# DAC.net
KiCad netlist of a schematic drawn in Altium Designer
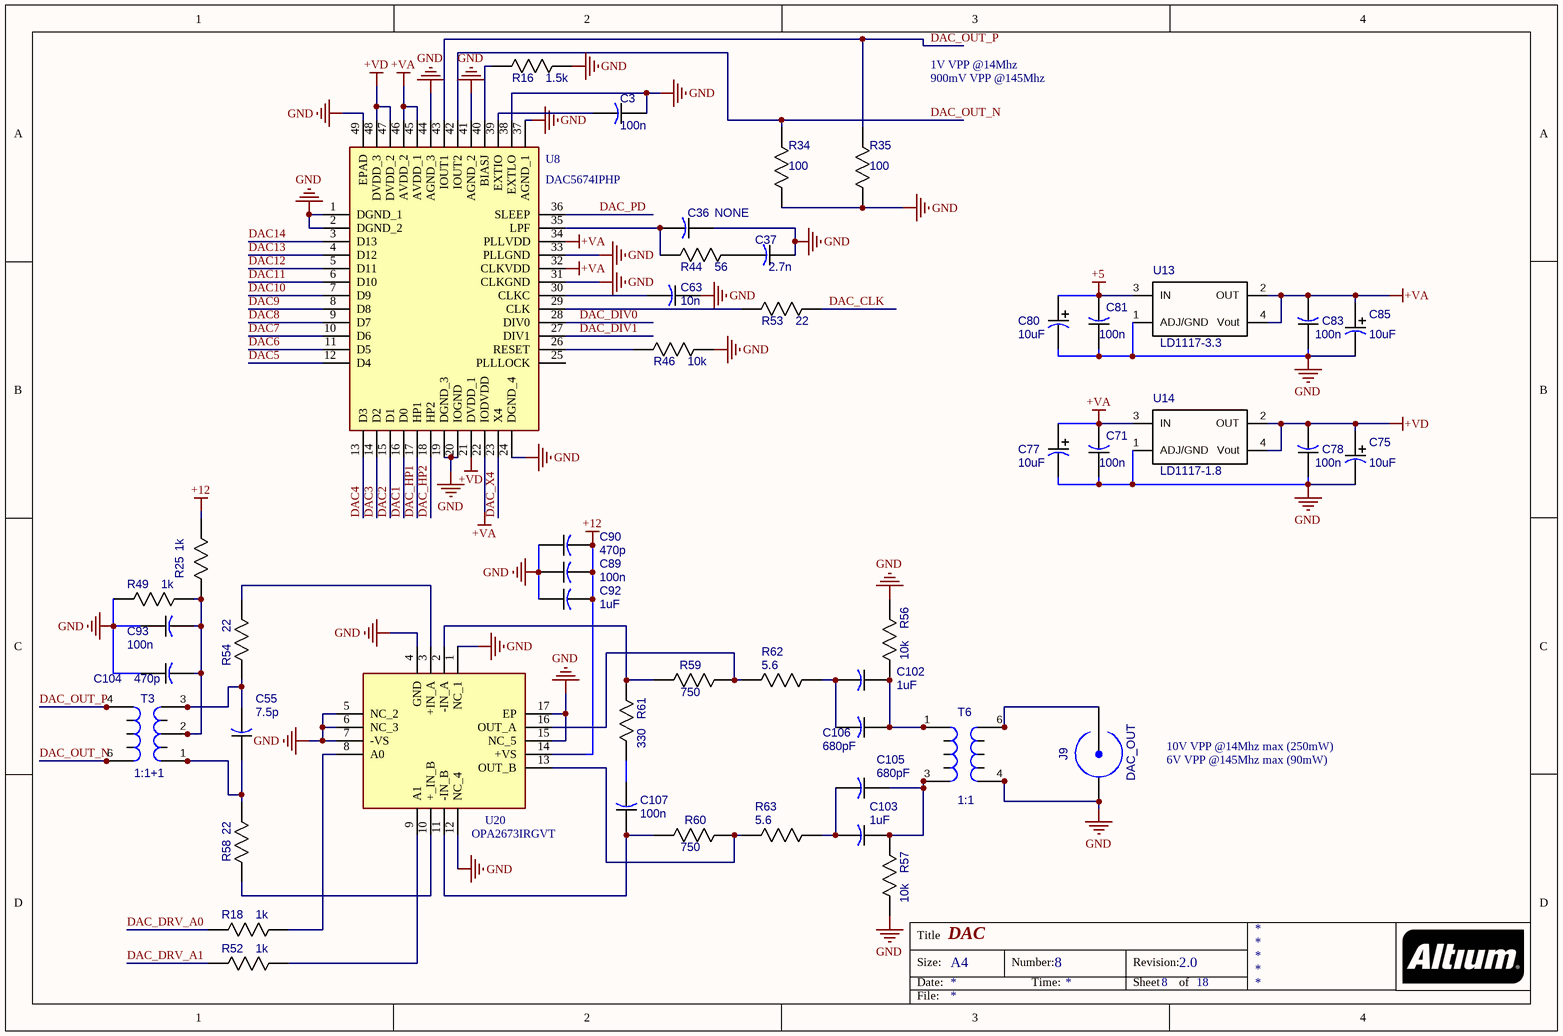
[diagram p0: DAC.SchDoc]

(export (version "E")
  (design (tool "Eeschema 10.0.6"))
  (components
    (comp (ref "C3")
      (value "100n")
      (footprint "CAP_0805")
      (description "CAP_0805")
      (libsource (lib "*") (part "CAP_0805"))
    )
    (comp (ref "C36")
      (value "NONE")
      (footprint "CAP_0805")
      (description "CAP_0805")
      (libsource (lib "*") (part "CAP_0805"))
    )
    (comp (ref "C37")
      (value "2.7n")
      (footprint "CAP_0805")
      (description "CAP_0805")
      (libsource (lib "*") (part "CAP_0805"))
    )
    (comp (ref "C55")
      (value "7.5p")
      (footprint "CAP_0805")
      (description "CAP_0805")
      (libsource (lib "*") (part "CAP_0805"))
    )
    (comp (ref "C63")
      (value "10n")
      (footprint "CAP_0805")
      (description "CAP_0805")
      (libsource (lib "*") (part "CAP_0805"))
    )
    (comp (ref "C71")
      (value "100n")
      (footprint "CAP_0805")
      (description "CAP_0805")
      (libsource (lib "*") (part "CAP_0805"))
    )
    (comp (ref "C75")
      (value "10uF")
      (footprint "EEEFC_sizeB")
      (description "EEEFC_sizeB")
      (libsource (lib "*") (part "EEEFC_sizeB"))
    )
    (comp (ref "C77")
      (value "10uF")
      (footprint "EEEFC_sizeB")
      (description "EEEFC_sizeB")
      (libsource (lib "*") (part "EEEFC_sizeB"))
    )
    (comp (ref "C78")
      (value "100n")
      (footprint "CAP_0805")
      (description "CAP_0805")
      (libsource (lib "*") (part "CAP_0805"))
    )
    (comp (ref "C80")
      (value "10uF")
      (footprint "EEEFC_sizeB")
      (description "EEEFC_sizeB")
      (libsource (lib "*") (part "EEEFC_sizeB"))
    )
    (comp (ref "C81")
      (value "100n")
      (footprint "CAP_0805")
      (description "CAP_0805")
      (libsource (lib "*") (part "CAP_0805"))
    )
    (comp (ref "C83")
      (value "100n")
      (footprint "CAP_0805")
      (description "CAP_0805")
      (libsource (lib "*") (part "CAP_0805"))
    )
    (comp (ref "C85")
      (value "10uF")
      (footprint "EEEFC_sizeB")
      (description "EEEFC_sizeB")
      (libsource (lib "*") (part "EEEFC_sizeB"))
    )
    (comp (ref "C89")
      (value "100n")
      (footprint "CAP_0805")
      (description "CAP_0805")
      (libsource (lib "*") (part "CAP_0805"))
    )
    (comp (ref "C90")
      (value "470p")
      (footprint "CAP_0805")
      (description "CAP_0805")
      (libsource (lib "*") (part "CAP_0805"))
    )
    (comp (ref "C92")
      (value "1uF")
      (footprint "CAP_0805")
      (description "CAP_0805")
      (libsource (lib "*") (part "CAP_0805"))
    )
    (comp (ref "C93")
      (value "100n")
      (footprint "CAP_0805")
      (description "CAP_0805")
      (libsource (lib "*") (part "CAP_0805"))
    )
    (comp (ref "C102")
      (value "1uF")
      (footprint "CAP_1206")
      (description "CAP_1206")
      (libsource (lib "*") (part "CAP_1206"))
    )
    (comp (ref "C103")
      (value "1uF")
      (footprint "CAP_1206")
      (description "CAP_1206")
      (libsource (lib "*") (part "CAP_1206"))
    )
    (comp (ref "C104")
      (value "470p")
      (footprint "CAP_0805")
      (description "CAP_0805")
      (libsource (lib "*") (part "CAP_0805"))
    )
    (comp (ref "C105")
      (value "680pF")
      (footprint "CAP_1206")
      (description "CAP_1206")
      (libsource (lib "*") (part "CAP_1206"))
    )
    (comp (ref "C106")
      (value "680pF")
      (footprint "CAP_1206")
      (description "CAP_1206")
      (libsource (lib "*") (part "CAP_1206"))
    )
    (comp (ref "C107")
      (value "100n")
      (footprint "CAP_0805")
      (description "CAP_0805")
      (libsource (lib "*") (part "CAP_0805"))
    )
    (comp (ref "J9")
      (value "DAC_OUT")
      (footprint "31-5431")
      (description "SMA")
      (libsource (lib "RF-UNIT_1") (part "31-5431"))
    )
    (comp (ref "R16")
      (value "1.5k")
      (footprint "RES_0805")
      (description "RES_0805")
      (libsource (lib "*") (part "RES_0805"))
    )
    (comp (ref "R18")
      (value "1k")
      (footprint "RES_0805")
      (description "RES_0805")
      (libsource (lib "*") (part "RES_0805"))
    )
    (comp (ref "R25")
      (value "1k")
      (footprint "RES_0805")
      (description "RES_0805")
      (libsource (lib "*") (part "RES_0805"))
    )
    (comp (ref "R34")
      (value "100")
      (footprint "RES_0805")
      (description "RES_0805")
      (libsource (lib "*") (part "RES_0805"))
    )
    (comp (ref "R35")
      (value "100")
      (footprint "RES_0805")
      (description "RES_0805")
      (libsource (lib "*") (part "RES_0805"))
    )
    (comp (ref "R44")
      (value "56")
      (footprint "RES_0805")
      (description "RES_0805")
      (libsource (lib "*") (part "RES_0805"))
    )
    (comp (ref "R46")
      (value "10k")
      (footprint "RES_0805")
      (description "RES_0805")
      (libsource (lib "*") (part "RES_0805"))
    )
    (comp (ref "R49")
      (value "1k")
      (footprint "RES_0805")
      (description "RES_0805")
      (libsource (lib "*") (part "RES_0805"))
    )
    (comp (ref "R52")
      (value "1k")
      (footprint "RES_0805")
      (description "RES_0805")
      (libsource (lib "*") (part "RES_0805"))
    )
    (comp (ref "R53")
      (value "22")
      (footprint "RES_0805")
      (description "RES_0805")
      (libsource (lib "*") (part "RES_0805"))
    )
    (comp (ref "R54")
      (value "22")
      (footprint "RES_0805")
      (description "RES_0805")
      (libsource (lib "*") (part "RES_0805"))
    )
    (comp (ref "R56")
      (value "10k")
      (footprint "RES_0805")
      (description "RES_0805")
      (libsource (lib "*") (part "RES_0805"))
    )
    (comp (ref "R57")
      (value "10k")
      (footprint "RES_0805")
      (description "RES_0805")
      (libsource (lib "*") (part "RES_0805"))
    )
    (comp (ref "R58")
      (value "22")
      (footprint "RES_0805")
      (description "RES_0805")
      (libsource (lib "*") (part "RES_0805"))
    )
    (comp (ref "R59")
      (value "750")
      (footprint "RES_0805")
      (description "RES_0805")
      (libsource (lib "*") (part "RES_0805"))
    )
    (comp (ref "R60")
      (value "750")
      (footprint "RES_0805")
      (description "RES_0805")
      (libsource (lib "*") (part "RES_0805"))
    )
    (comp (ref "R61")
      (value "330")
      (footprint "RES_0805")
      (description "RES_0805")
      (libsource (lib "*") (part "RES_0805"))
    )
    (comp (ref "R62")
      (value "5.6")
      (footprint "RES_1206")
      (description "RES_1206")
      (libsource (lib "*") (part "RES_1206"))
    )
    (comp (ref "R63")
      (value "5.6")
      (footprint "RES_1206")
      (description "RES_1206")
      (libsource (lib "*") (part "RES_1206"))
    )
    (comp (ref "T3")
      (value "1:1+1")
      (footprint "TRANSF_ACORE2")
      (description "Transformer")
      (libsource (lib "MOTHERBOARD_1") (part "TRANSF_ACORE2"))
    )
    (comp (ref "T6")
      (value "1:1")
      (footprint "TRANSF_ACORE")
      (description "Transformer")
      (libsource (lib "MOTHERBOARD_1") (part "TRANSF_ACORE"))
    )
    (comp (ref "U8")
      (value "DAC5674IPHP")
      (footprint "SamacSys:QFP50P900X900X100-49N")
      (description "Integrated Circuit")
      (libsource (lib "*") (part "DAC5674IPHP"))
    )
    (comp (ref "U13")
      (value "LD1117-3.3")
      (footprint "LT1117CST-3.3")
      (description "LT1117CST-3.3")
      (libsource (lib "*") (part "LT1117CST-3.3"))
    )
    (comp (ref "U14")
      (value "LD1117-1.8")
      (footprint "LT1117CST-3.3")
      (description "LT1117CST-1.8")
      (libsource (lib "*") (part "LT1117CST-3.3"))
    )
    (comp (ref "U20")
      (value "OPA2673IRGVT")
      (footprint "SamacSys:QFN65P400X400X100-17N-D")
      (description "Integrated Circuit")
      (fields
        (field (name "MOUSER PART NUMBER") "595-OPA2673IRGVT")
        (field (name "RS PART NUMBER") "8122587P")
      )
      (libsource (lib "*") (part "OPA2673IRGVT"))
    )
  )
  (nets
    (net (code "1") (name "+5") (class "Default")
      (node (ref "C80") (pin "1") (pinfunction "PLUS_1") (pintype "passive"))
      (node (ref "C81") (pin "2") (pinfunction "2_2") (pintype "passive"))
      (node (ref "U13") (pin "3") (pinfunction "IN_3") (pintype "passive"))
    )
    (net (code "2") (name "+12") (class "Default")
      (node (ref "C89") (pin "2") (pinfunction "2_2") (pintype "passive"))
      (node (ref "C90") (pin "2") (pinfunction "2_2") (pintype "passive"))
      (node (ref "C92") (pin "2") (pinfunction "2_2") (pintype "passive"))
      (node (ref "R25") (pin "2") (pinfunction "2_2") (pintype "passive"))
      (node (ref "U20") (pin "14") (pinfunction "+VS_14") (pintype "passive"))
    )
    (net (code "3") (name "+VA") (class "Default")
      (node (ref "C71") (pin "2") (pinfunction "2_2") (pintype "passive"))
      (node (ref "C77") (pin "1") (pinfunction "PLUS_1") (pintype "passive"))
      (node (ref "C83") (pin "2") (pinfunction "2_2") (pintype "passive"))
      (node (ref "C85") (pin "1") (pinfunction "PLUS_1") (pintype "passive"))
      (node (ref "U13") (pin "2") (pinfunction "OUT_2") (pintype "passive"))
      (node (ref "U13") (pin "4") (pinfunction "Vout_4") (pintype "passive"))
      (node (ref "U14") (pin "3") (pinfunction "IN_3") (pintype "passive"))
      (node (ref "U8") (pin "22") (pinfunction "IODVDD_22") (pintype "passive"))
      (node (ref "U8") (pin "32") (pinfunction "CLKVDD_32") (pintype "passive"))
      (node (ref "U8") (pin "34") (pinfunction "PLLVDD_34") (pintype "passive"))
      (node (ref "U8") (pin "45") (pinfunction "AVDD_1_45") (pintype "passive"))
      (node (ref "U8") (pin "46") (pinfunction "AVDD_2_46") (pintype "passive"))
    )
    (net (code "4") (name "+VD") (class "Default")
      (node (ref "C75") (pin "1") (pinfunction "PLUS_1") (pintype "passive"))
      (node (ref "C78") (pin "2") (pinfunction "2_2") (pintype "passive"))
      (node (ref "U14") (pin "2") (pinfunction "OUT_2") (pintype "passive"))
      (node (ref "U14") (pin "4") (pinfunction "Vout_4") (pintype "passive"))
      (node (ref "U8") (pin "21") (pinfunction "DVDD_1_21") (pintype "passive"))
      (node (ref "U8") (pin "47") (pinfunction "DVDD_2_47") (pintype "passive"))
      (node (ref "U8") (pin "48") (pinfunction "DVDD_3_48") (pintype "passive"))
    )
    (net (code "5") (name "/DAC1") (class "Default")
      (node (ref "U8") (pin "16") (pinfunction "D0_16") (pintype "passive"))
    )
    (net (code "6") (name "/DAC2") (class "Default")
      (node (ref "U8") (pin "15") (pinfunction "D1_15") (pintype "passive"))
    )
    (net (code "7") (name "/DAC3") (class "Default")
      (node (ref "U8") (pin "14") (pinfunction "D2_14") (pintype "passive"))
    )
    (net (code "8") (name "/DAC4") (class "Default")
      (node (ref "U8") (pin "13") (pinfunction "D3_13") (pintype "passive"))
    )
    (net (code "9") (name "/DAC5") (class "Default")
      (node (ref "U8") (pin "12") (pinfunction "D4_12") (pintype "passive"))
    )
    (net (code "10") (name "/DAC6") (class "Default")
      (node (ref "U8") (pin "11") (pinfunction "D5_11") (pintype "passive"))
    )
    (net (code "11") (name "/DAC7") (class "Default")
      (node (ref "U8") (pin "10") (pinfunction "D6_10") (pintype "passive"))
    )
    (net (code "12") (name "/DAC8") (class "Default")
      (node (ref "U8") (pin "9") (pinfunction "D7_9") (pintype "passive"))
    )
    (net (code "13") (name "/DAC9") (class "Default")
      (node (ref "U8") (pin "8") (pinfunction "D8_8") (pintype "passive"))
    )
    (net (code "14") (name "/DAC10") (class "Default")
      (node (ref "U8") (pin "7") (pinfunction "D9_7") (pintype "passive"))
    )
    (net (code "15") (name "/DAC11") (class "Default")
      (node (ref "U8") (pin "6") (pinfunction "D10_6") (pintype "passive"))
    )
    (net (code "16") (name "/DAC12") (class "Default")
      (node (ref "U8") (pin "5") (pinfunction "D11_5") (pintype "passive"))
    )
    (net (code "17") (name "/DAC13") (class "Default")
      (node (ref "U8") (pin "4") (pinfunction "D12_4") (pintype "passive"))
    )
    (net (code "18") (name "/DAC14") (class "Default")
      (node (ref "U8") (pin "3") (pinfunction "D13_3") (pintype "passive"))
    )
    (net (code "19") (name "/DAC_CLK") (class "Default")
      (node (ref "R53") (pin "1") (pinfunction "1_1") (pintype "passive"))
    )
    (net (code "20") (name "/DAC_DIV0") (class "Default")
      (node (ref "U8") (pin "28") (pinfunction "DIV0_28") (pintype "passive"))
    )
    (net (code "21") (name "/DAC_DIV1") (class "Default")
      (node (ref "U8") (pin "27") (pinfunction "DIV1_27") (pintype "passive"))
    )
    (net (code "22") (name "/DAC_DRV_A0") (class "Default")
      (node (ref "R18") (pin "1") (pinfunction "1_1") (pintype "passive"))
    )
    (net (code "23") (name "/DAC_DRV_A1") (class "Default")
      (node (ref "R52") (pin "1") (pinfunction "1_1") (pintype "passive"))
    )
    (net (code "24") (name "/DAC_HP1") (class "Default")
      (node (ref "U8") (pin "17") (pinfunction "HP1_17") (pintype "passive"))
    )
    (net (code "25") (name "/DAC_HP2") (class "Default")
      (node (ref "U8") (pin "18") (pinfunction "HP2_18") (pintype "passive"))
    )
    (net (code "26") (name "/DAC_OUT_N") (class "Default")
      (node (ref "R34") (pin "2") (pinfunction "2_2") (pintype "passive"))
      (node (ref "T3") (pin "10") (pinfunction "0_10") (pintype "passive"))
      (node (ref "T3") (pin "6") (pinfunction "P2_6") (pintype "passive"))
      (node (ref "U8") (pin "42") (pinfunction "IOUT2_42") (pintype "passive"))
    )
    (net (code "27") (name "/DAC_OUT_P") (class "Default")
      (node (ref "R35") (pin "2") (pinfunction "2_2") (pintype "passive"))
      (node (ref "T3") (pin "11") (pinfunction "0_11") (pintype "passive"))
      (node (ref "T3") (pin "4") (pinfunction "P1_4") (pintype "passive"))
      (node (ref "U8") (pin "43") (pinfunction "IOUT1_43") (pintype "passive"))
    )
    (net (code "28") (name "/DAC_PD") (class "Default")
      (node (ref "U8") (pin "36") (pinfunction "SLEEP_36") (pintype "passive"))
    )
    (net (code "29") (name "/DAC_X4") (class "Default")
      (node (ref "U8") (pin "23") (pinfunction "X4_23") (pintype "passive"))
    )
    (net (code "30") (name "GND") (class "Default")
      (node (ref "C104") (pin "1") (pinfunction "1_1") (pintype "passive"))
      (node (ref "C3") (pin "1") (pinfunction "1_1") (pintype "passive"))
      (node (ref "C36") (pin "1") (pinfunction "1_1") (pintype "passive"))
      (node (ref "C37") (pin "1") (pinfunction "1_1") (pintype "passive"))
      (node (ref "C63") (pin "1") (pinfunction "1_1") (pintype "passive"))
      (node (ref "C71") (pin "1") (pinfunction "1_1") (pintype "passive"))
      (node (ref "C75") (pin "2") (pinfunction "MINUS_2") (pintype "passive"))
      (node (ref "C77") (pin "2") (pinfunction "MINUS_2") (pintype "passive"))
      (node (ref "C78") (pin "1") (pinfunction "1_1") (pintype "passive"))
      (node (ref "C80") (pin "2") (pinfunction "MINUS_2") (pintype "passive"))
      (node (ref "C81") (pin "1") (pinfunction "1_1") (pintype "passive"))
      (node (ref "C83") (pin "1") (pinfunction "1_1") (pintype "passive"))
      (node (ref "C85") (pin "2") (pinfunction "MINUS_2") (pintype "passive"))
      (node (ref "C89") (pin "1") (pinfunction "1_1") (pintype "passive"))
      (node (ref "C90") (pin "1") (pinfunction "1_1") (pintype "passive"))
      (node (ref "C92") (pin "1") (pinfunction "1_1") (pintype "passive"))
      (node (ref "C93") (pin "1") (pinfunction "1_1") (pintype "passive"))
      (node (ref "J9") (pin "1") (pinfunction "GND_1") (pintype "passive"))
      (node (ref "J9") (pin "2") (pinfunction "GND_2") (pintype "passive"))
      (node (ref "J9") (pin "3") (pinfunction "GND_3") (pintype "passive"))
      (node (ref "J9") (pin "4") (pinfunction "GND_4") (pintype "passive"))
      (node (ref "R16") (pin "1") (pinfunction "1_1") (pintype "passive"))
      (node (ref "R34") (pin "1") (pinfunction "1_1") (pintype "passive"))
      (node (ref "R35") (pin "1") (pinfunction "1_1") (pintype "passive"))
      (node (ref "R46") (pin "1") (pinfunction "1_1") (pintype "passive"))
      (node (ref "R49") (pin "2") (pinfunction "2_2") (pintype "passive"))
      (node (ref "R56") (pin "1") (pinfunction "1_1") (pintype "passive"))
      (node (ref "R57") (pin "2") (pinfunction "2_2") (pintype "passive"))
      (node (ref "T6") (pin "11") (pinfunction "0_11") (pintype "passive"))
      (node (ref "T6") (pin "4") (pinfunction "S2_4") (pintype "passive"))
      (node (ref "U13") (pin "1") (pinfunction "ADJ/GND_1") (pintype "passive"))
      (node (ref "U14") (pin "1") (pinfunction "ADJ/GND_1") (pintype "passive"))
      (node (ref "U20") (pin "1") (pinfunction "NC_1_1") (pintype "passive"))
      (node (ref "U20") (pin "12") (pinfunction "NC_4_12") (pintype "passive"))
      (node (ref "U20") (pin "15") (pinfunction "NC_5_15") (pintype "passive"))
      (node (ref "U20") (pin "17") (pinfunction "EP_17") (pintype "passive"))
      (node (ref "U20") (pin "4") (pinfunction "GND_4") (pintype "passive"))
      (node (ref "U20") (pin "5") (pinfunction "NC_2_5") (pintype "passive"))
      (node (ref "U20") (pin "6") (pinfunction "NC_3_6") (pintype "passive"))
      (node (ref "U20") (pin "7") (pinfunction "-VS_7") (pintype "passive"))
      (node (ref "U8") (pin "1") (pinfunction "DGND_1_1") (pintype "passive"))
      (node (ref "U8") (pin "19") (pinfunction "DGND_3_19") (pintype "passive"))
      (node (ref "U8") (pin "2") (pinfunction "DGND_2_2") (pintype "passive"))
      (node (ref "U8") (pin "20") (pinfunction "IOGND_20") (pintype "passive"))
      (node (ref "U8") (pin "24") (pinfunction "DGND_4_24") (pintype "passive"))
      (node (ref "U8") (pin "31") (pinfunction "CLKGND_31") (pintype "passive"))
      (node (ref "U8") (pin "33") (pinfunction "PLLGND_33") (pintype "passive"))
      (node (ref "U8") (pin "37") (pinfunction "AGND_1_37") (pintype "passive"))
      (node (ref "U8") (pin "38") (pinfunction "EXTLO_38") (pintype "passive"))
      (node (ref "U8") (pin "41") (pinfunction "AGND_2_41") (pintype "passive"))
      (node (ref "U8") (pin "44") (pinfunction "AGND_3_44") (pintype "passive"))
      (node (ref "U8") (pin "49") (pinfunction "EPAD_49") (pintype "passive"))
    )
    (net (code "31") (name "Net-(C37-Pad2)") (class "Default")
      (node (ref "C37") (pin "2") (pinfunction "2_2") (pintype "passive"))
      (node (ref "R44") (pin "1") (pinfunction "1_1") (pintype "passive"))
    )
    (net (code "32") (name "Net-(C102-Pad2)") (class "Default")
      (node (ref "C102") (pin "2") (pinfunction "2_2") (pintype "passive"))
      (node (ref "C106") (pin "2") (pinfunction "2_2") (pintype "passive"))
      (node (ref "R62") (pin "1") (pinfunction "1_1") (pintype "passive"))
    )
    (net (code "33") (name "Net-(C103-Pad2)") (class "Default")
      (node (ref "C103") (pin "2") (pinfunction "2_2") (pintype "passive"))
      (node (ref "C105") (pin "2") (pinfunction "2_2") (pintype "passive"))
      (node (ref "R63") (pin "1") (pinfunction "1_1") (pintype "passive"))
    )
    (net (code "34") (name "Net-(C107-Pad2)") (class "Default")
      (node (ref "C107") (pin "2") (pinfunction "2_2") (pintype "passive"))
      (node (ref "R61") (pin "2") (pinfunction "2_2") (pintype "passive"))
    )
    (net (code "35") (name "Net-(J9-CON)") (class "Default")
      (node (ref "J9") (pin "5") (pinfunction "CON_5") (pintype "passive"))
      (node (ref "T6") (pin "10") (pinfunction "0_10") (pintype "passive"))
      (node (ref "T6") (pin "6") (pinfunction "S1_6") (pintype "passive"))
    )
    (net (code "36") (name "Net-(T3-S1)") (class "Default")
      (node (ref "C55") (pin "2") (pinfunction "2_2") (pintype "passive"))
      (node (ref "R54") (pin "1") (pinfunction "1_1") (pintype "passive"))
      (node (ref "T3") (pin "3") (pinfunction "S1_3") (pintype "passive"))
      (node (ref "T3") (pin "9") (pinfunction "0_9") (pintype "passive"))
    )
    (net (code "37") (name "Net-(T3-S2)") (class "Default")
      (node (ref "C104") (pin "2") (pinfunction "2_2") (pintype "passive"))
      (node (ref "C93") (pin "2") (pinfunction "2_2") (pintype "passive"))
      (node (ref "R25") (pin "1") (pinfunction "1_1") (pintype "passive"))
      (node (ref "R49") (pin "1") (pinfunction "1_1") (pintype "passive"))
      (node (ref "T3") (pin "2") (pinfunction "S2_2") (pintype "passive"))
      (node (ref "T3") (pin "8") (pinfunction "0_8") (pintype "passive"))
    )
    (net (code "38") (name "Net-(T3-S3)") (class "Default")
      (node (ref "C55") (pin "1") (pinfunction "1_1") (pintype "passive"))
      (node (ref "R58") (pin "2") (pinfunction "2_2") (pintype "passive"))
      (node (ref "T3") (pin "1") (pinfunction "S3_1") (pintype "passive"))
      (node (ref "T3") (pin "7") (pinfunction "0_7") (pintype "passive"))
    )
    (net (code "39") (name "Net-(T6-P1)") (class "Default")
      (node (ref "C102") (pin "1") (pinfunction "1_1") (pintype "passive"))
      (node (ref "C106") (pin "1") (pinfunction "1_1") (pintype "passive"))
      (node (ref "R56") (pin "2") (pinfunction "2_2") (pintype "passive"))
      (node (ref "T6") (pin "1") (pinfunction "P1_1") (pintype "passive"))
      (node (ref "T6") (pin "7") (pinfunction "0_7") (pintype "passive"))
    )
    (net (code "40") (name "Net-(T6-P2)") (class "Default")
      (node (ref "C103") (pin "1") (pinfunction "1_1") (pintype "passive"))
      (node (ref "C105") (pin "1") (pinfunction "1_1") (pintype "passive"))
      (node (ref "R57") (pin "1") (pinfunction "1_1") (pintype "passive"))
      (node (ref "T6") (pin "3") (pinfunction "P2_3") (pintype "passive"))
      (node (ref "T6") (pin "9") (pinfunction "0_9") (pintype "passive"))
    )
    (net (code "41") (name "Net-(U8-BIASJ)") (class "Default")
      (node (ref "R16") (pin "2") (pinfunction "2_2") (pintype "passive"))
      (node (ref "U8") (pin "40") (pinfunction "BIASJ_40") (pintype "passive"))
    )
    (net (code "42") (name "Net-(U8-CLK)") (class "Default")
      (node (ref "R53") (pin "2") (pinfunction "2_2") (pintype "passive"))
      (node (ref "U8") (pin "29") (pinfunction "CLK_29") (pintype "passive"))
    )
    (net (code "43") (name "Net-(U8-CLKC)") (class "Default")
      (node (ref "C63") (pin "2") (pinfunction "2_2") (pintype "passive"))
      (node (ref "U8") (pin "30") (pinfunction "CLKC_30") (pintype "passive"))
    )
    (net (code "44") (name "Net-(U8-EXTIO)") (class "Default")
      (node (ref "C3") (pin "2") (pinfunction "2_2") (pintype "passive"))
      (node (ref "U8") (pin "39") (pinfunction "EXTIO_39") (pintype "passive"))
    )
    (net (code "45") (name "Net-(U8-LPF)") (class "Default")
      (node (ref "C36") (pin "2") (pinfunction "2_2") (pintype "passive"))
      (node (ref "R44") (pin "2") (pinfunction "2_2") (pintype "passive"))
      (node (ref "U8") (pin "35") (pinfunction "LPF_35") (pintype "passive"))
    )
    (net (code "46") (name "Net-(U8-RESET)") (class "Default")
      (node (ref "R46") (pin "2") (pinfunction "2_2") (pintype "passive"))
      (node (ref "U8") (pin "26") (pinfunction "RESET_26") (pintype "passive"))
    )
    (net (code "47") (name "Net-(U20-+IN_A)") (class "Default")
      (node (ref "R54") (pin "2") (pinfunction "2_2") (pintype "passive"))
      (node (ref "U20") (pin "3") (pinfunction "+IN_A_3") (pintype "passive"))
    )
    (net (code "48") (name "Net-(U20-+_IN_B)") (class "Default")
      (node (ref "R58") (pin "1") (pinfunction "1_1") (pintype "passive"))
      (node (ref "U20") (pin "10") (pinfunction "+_IN_B_10") (pintype "passive"))
    )
    (net (code "49") (name "Net-(U20--IN_A)") (class "Default")
      (node (ref "R59") (pin "2") (pinfunction "2_2") (pintype "passive"))
      (node (ref "R61") (pin "1") (pinfunction "1_1") (pintype "passive"))
      (node (ref "U20") (pin "2") (pinfunction "-IN_A_2") (pintype "passive"))
    )
    (net (code "50") (name "Net-(U20--IN_B)") (class "Default")
      (node (ref "C107") (pin "1") (pinfunction "1_1") (pintype "passive"))
      (node (ref "R60") (pin "2") (pinfunction "2_2") (pintype "passive"))
      (node (ref "U20") (pin "11") (pinfunction "-IN_B_11") (pintype "passive"))
    )
    (net (code "51") (name "Net-(U20-A0)") (class "Default")
      (node (ref "R18") (pin "2") (pinfunction "2_2") (pintype "passive"))
      (node (ref "U20") (pin "8") (pinfunction "A0_8") (pintype "passive"))
    )
    (net (code "52") (name "Net-(U20-A1)") (class "Default")
      (node (ref "R52") (pin "2") (pinfunction "2_2") (pintype "passive"))
      (node (ref "U20") (pin "9") (pinfunction "A1_9") (pintype "passive"))
    )
    (net (code "53") (name "Net-(U20-OUT_A)") (class "Default")
      (node (ref "R59") (pin "1") (pinfunction "1_1") (pintype "passive"))
      (node (ref "R62") (pin "2") (pinfunction "2_2") (pintype "passive"))
      (node (ref "U20") (pin "16") (pinfunction "OUT_A_16") (pintype "passive"))
    )
    (net (code "54") (name "Net-(U20-OUT_B)") (class "Default")
      (node (ref "R60") (pin "1") (pinfunction "1_1") (pintype "passive"))
      (node (ref "R63") (pin "2") (pinfunction "2_2") (pintype "passive"))
      (node (ref "U20") (pin "13") (pinfunction "OUT_B_13") (pintype "passive"))
    )
    (net (code "55") (name "unconnected-(T6-0-Pad8)") (class "Default")
      (node (ref "T6") (pin "8") (pinfunction "0_8") (pintype "passive"))
    )
    (net (code "56") (name "unconnected-(U8-PLLLOCK-Pad25)") (class "Default")
      (node (ref "U8") (pin "25") (pinfunction "PLLLOCK_25") (pintype "passive"))
    )
  )
)
